# signal-board.net
KiCad netlist of a schematic drawn in EAGLE
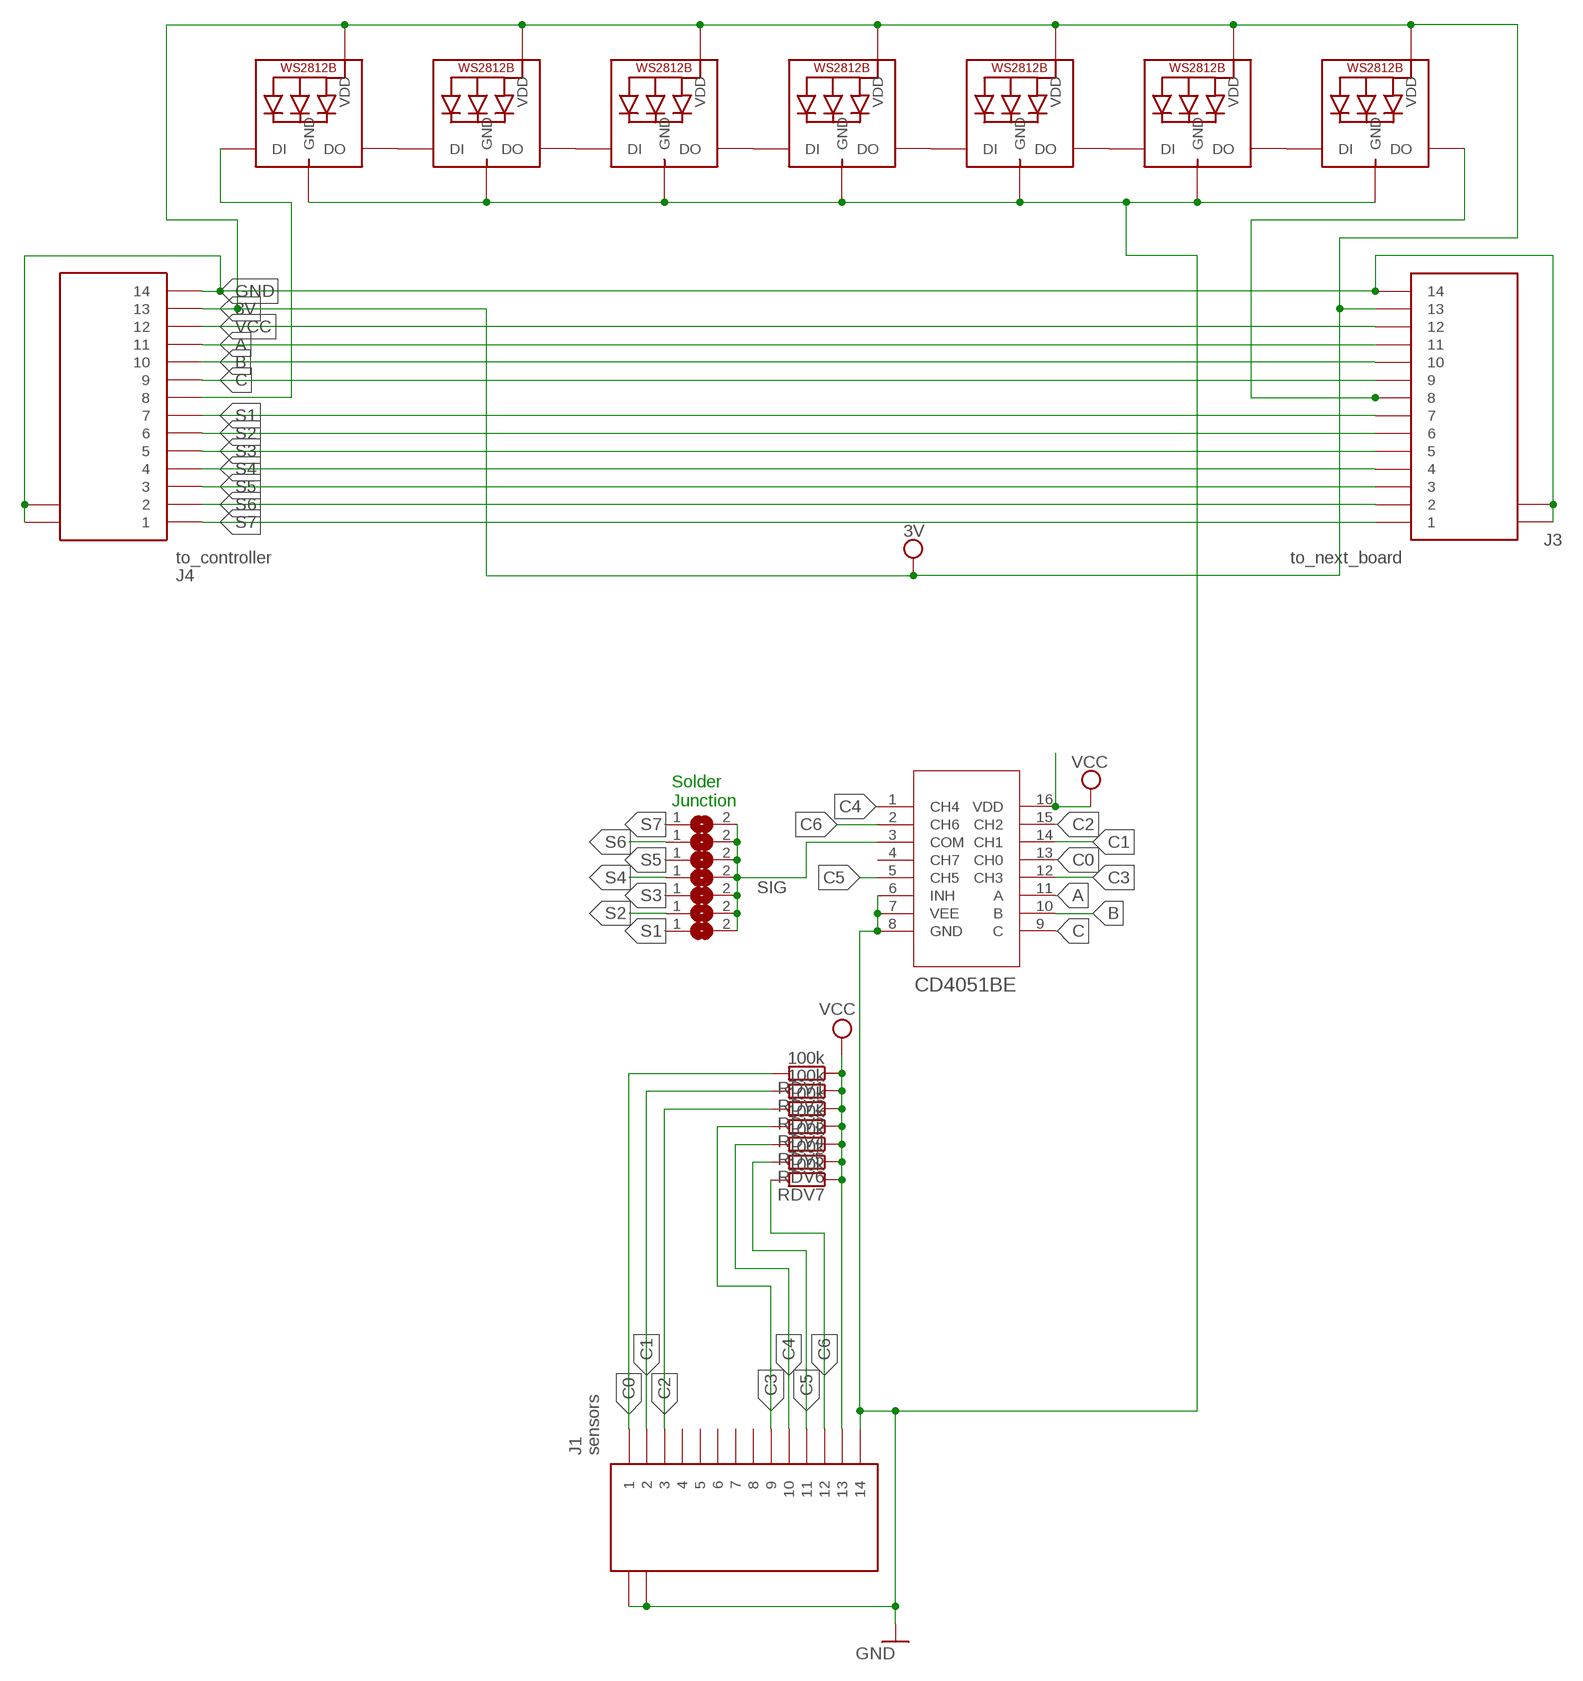
[diagram p0: schematic, sheet 1]

(export (version "E")
  (design (tool "Eeschema 10.0.6"))
  (components
    (comp (ref "J1")
      (value "sensors")
      (footprint "eagle-import:686114148922")
      (fields
        (field (name "MANUFACTURER_PART_NUMBER") "686114148922")
        (field (name "MOUSER_PART_NUMBER") "710-686114148922")
      )
      (libsource (lib "eagle-import") (part "686114148922"))
    )
    (comp (ref "J3")
      (value "to_next_board")
      (footprint "eagle-import:686114148922")
      (fields
        (field (name "MANUFACTURER_PART_NUMBER") "686114148922")
        (field (name "MOUSER_PART_NUMBER") "710-686114148922")
      )
      (libsource (lib "eagle-import") (part "686114148922"))
    )
    (comp (ref "J4")
      (value "to_controller")
      (footprint "eagle-import:686114148922")
      (fields
        (field (name "MANUFACTURER_PART_NUMBER") "686114148922")
        (field (name "MOUSER_PART_NUMBER") "710-686114148922")
      )
      (libsource (lib "eagle-import") (part "686114148922"))
    )
    (comp (ref "LED1")
      (value "WS2812B3535")
      (footprint "eagle-import:LED3535")
      (libsource (lib "eagle-import") (part "WS2812B3535"))
    )
    (comp (ref "LED2")
      (value "WS2812B3535")
      (footprint "eagle-import:LED3535")
      (libsource (lib "eagle-import") (part "WS2812B3535"))
    )
    (comp (ref "LED3")
      (value "WS2812B3535")
      (footprint "eagle-import:LED3535")
      (libsource (lib "eagle-import") (part "WS2812B3535"))
    )
    (comp (ref "LED4")
      (value "WS2812B3535")
      (footprint "eagle-import:LED3535")
      (libsource (lib "eagle-import") (part "WS2812B3535"))
    )
    (comp (ref "LED5")
      (value "WS2812B3535")
      (footprint "eagle-import:LED3535")
      (libsource (lib "eagle-import") (part "WS2812B3535"))
    )
    (comp (ref "LED6")
      (value "WS2812B3535")
      (footprint "eagle-import:LED3535")
      (libsource (lib "eagle-import") (part "WS2812B3535"))
    )
    (comp (ref "LED7")
      (value "WS2812B3535")
      (footprint "eagle-import:LED3535")
      (libsource (lib "eagle-import") (part "WS2812B3535"))
    )
    (comp (ref "RDV1")
      (value "100k")
      (footprint "eagle-import:0207_10")
      (libsource (lib "eagle-import") (part "R-EU_0207/10"))
    )
    (comp (ref "RDV2")
      (value "100k")
      (footprint "eagle-import:0207_10")
      (libsource (lib "eagle-import") (part "R-EU_0207/10"))
    )
    (comp (ref "RDV3")
      (value "100k")
      (footprint "eagle-import:0207_10")
      (libsource (lib "eagle-import") (part "R-EU_0207/10"))
    )
    (comp (ref "RDV4")
      (value "100k")
      (footprint "eagle-import:0207_10")
      (libsource (lib "eagle-import") (part "R-EU_0207/10"))
    )
    (comp (ref "RDV5")
      (value "100k")
      (footprint "eagle-import:0207_10")
      (libsource (lib "eagle-import") (part "R-EU_0207/10"))
    )
    (comp (ref "RDV6")
      (value "100k")
      (footprint "eagle-import:0207_10")
      (libsource (lib "eagle-import") (part "R-EU_0207/10"))
    )
    (comp (ref "RDV7")
      (value "100k")
      (footprint "eagle-import:0207_10")
      (libsource (lib "eagle-import") (part "R-EU_0207/10"))
    )
    (comp (ref "SJ1") (value "SJ") (footprint "eagle-import:SJ") (libsource (lib "eagle-import") (part "SJ")))
    (comp (ref "SJ2") (value "SJ") (footprint "eagle-import:SJ") (libsource (lib "eagle-import") (part "SJ")))
    (comp (ref "SJ3") (value "SJ") (footprint "eagle-import:SJ") (libsource (lib "eagle-import") (part "SJ")))
    (comp (ref "SJ4") (value "SJ") (footprint "eagle-import:SJ") (libsource (lib "eagle-import") (part "SJ")))
    (comp (ref "SJ5") (value "SJ") (footprint "eagle-import:SJ") (libsource (lib "eagle-import") (part "SJ")))
    (comp (ref "SJ6") (value "SJ") (footprint "eagle-import:SJ") (libsource (lib "eagle-import") (part "SJ")))
    (comp (ref "SJ7") (value "SJ") (footprint "eagle-import:SJ") (libsource (lib "eagle-import") (part "SJ")))
    (comp (ref "U1")
      (value "CD4051BE")
      (footprint "eagle-import:N16")
      (fields (field (name "COPYRIGHT") "Copyright (C) 2024 Ultra Librarian. All rights reserved."))
      (libsource (lib "eagle-import") (part "CD4051BE"))
    )
  )
  (nets
    (net (code "1") (name "/SIG") (class "Default")
      (node (ref "SJ1") (pin "2") (pinfunction "2_2") (pintype "passive"))
      (node (ref "SJ2") (pin "2") (pinfunction "2_2") (pintype "passive"))
      (node (ref "SJ3") (pin "2") (pinfunction "2_2") (pintype "passive"))
      (node (ref "SJ4") (pin "2") (pinfunction "2_2") (pintype "passive"))
      (node (ref "SJ5") (pin "2") (pinfunction "2_2") (pintype "passive"))
      (node (ref "SJ6") (pin "2") (pinfunction "2_2") (pintype "passive"))
      (node (ref "SJ7") (pin "2") (pinfunction "2_2") (pintype "passive"))
      (node (ref "U1") (pin "3") (pinfunction "COM_3") (pintype "bidirectional"))
    )
    (net (code "2") (name "3V") (class "Default")
      (node (ref "J3") (pin "13") (pinfunction "13_13") (pintype "bidirectional"))
      (node (ref "J4") (pin "13") (pinfunction "13_13") (pintype "bidirectional"))
      (node (ref "LED1") (pin "2") (pinfunction "VDD_2") (pintype "power_in"))
      (node (ref "LED2") (pin "2") (pinfunction "VDD_2") (pintype "power_in"))
      (node (ref "LED3") (pin "2") (pinfunction "VDD_2") (pintype "power_in"))
      (node (ref "LED4") (pin "2") (pinfunction "VDD_2") (pintype "power_in"))
      (node (ref "LED5") (pin "2") (pinfunction "VDD_2") (pintype "power_in"))
      (node (ref "LED6") (pin "2") (pinfunction "VDD_2") (pintype "power_in"))
      (node (ref "LED7") (pin "2") (pinfunction "VDD_2") (pintype "power_in"))
    )
    (net (code "3") (name "A") (class "Default")
      (node (ref "J3") (pin "11") (pinfunction "11_11") (pintype "bidirectional"))
      (node (ref "J4") (pin "11") (pinfunction "11_11") (pintype "bidirectional"))
      (node (ref "U1") (pin "11") (pinfunction "A_11") (pintype "passive"))
    )
    (net (code "4") (name "B") (class "Default")
      (node (ref "J3") (pin "10") (pinfunction "10_10") (pintype "bidirectional"))
      (node (ref "J4") (pin "10") (pinfunction "10_10") (pintype "bidirectional"))
      (node (ref "U1") (pin "10") (pinfunction "B_10") (pintype "passive"))
    )
    (net (code "5") (name "C") (class "Default")
      (node (ref "J3") (pin "9") (pinfunction "9_9") (pintype "bidirectional"))
      (node (ref "J4") (pin "9") (pinfunction "9_9") (pintype "bidirectional"))
      (node (ref "U1") (pin "9") (pinfunction "C_9") (pintype "passive"))
    )
    (net (code "6") (name "C0") (class "Default")
      (node (ref "J1") (pin "1") (pinfunction "1_1") (pintype "bidirectional"))
      (node (ref "RDV1") (pin "2") (pinfunction "2_2") (pintype "passive"))
      (node (ref "U1") (pin "13") (pinfunction "CH0_13") (pintype "bidirectional"))
    )
    (net (code "7") (name "C1") (class "Default")
      (node (ref "J1") (pin "2") (pinfunction "2_2") (pintype "bidirectional"))
      (node (ref "RDV2") (pin "2") (pinfunction "2_2") (pintype "passive"))
      (node (ref "U1") (pin "14") (pinfunction "CH1_14") (pintype "bidirectional"))
    )
    (net (code "8") (name "C2") (class "Default")
      (node (ref "J1") (pin "3") (pinfunction "3_3") (pintype "bidirectional"))
      (node (ref "RDV3") (pin "2") (pinfunction "2_2") (pintype "passive"))
      (node (ref "U1") (pin "15") (pinfunction "CH2_15") (pintype "bidirectional"))
    )
    (net (code "9") (name "C3") (class "Default")
      (node (ref "J1") (pin "9") (pinfunction "9_9") (pintype "bidirectional"))
      (node (ref "RDV4") (pin "2") (pinfunction "2_2") (pintype "passive"))
      (node (ref "U1") (pin "12") (pinfunction "CH3_12") (pintype "bidirectional"))
    )
    (net (code "10") (name "C4") (class "Default")
      (node (ref "J1") (pin "10") (pinfunction "10_10") (pintype "bidirectional"))
      (node (ref "RDV5") (pin "2") (pinfunction "2_2") (pintype "passive"))
      (node (ref "U1") (pin "1") (pinfunction "CH4_1") (pintype "bidirectional"))
    )
    (net (code "11") (name "C5") (class "Default")
      (node (ref "J1") (pin "11") (pinfunction "11_11") (pintype "bidirectional"))
      (node (ref "RDV6") (pin "2") (pinfunction "2_2") (pintype "passive"))
      (node (ref "U1") (pin "5") (pinfunction "CH5_5") (pintype "bidirectional"))
    )
    (net (code "12") (name "C6") (class "Default")
      (node (ref "J1") (pin "12") (pinfunction "12_12") (pintype "bidirectional"))
      (node (ref "RDV7") (pin "2") (pinfunction "2_2") (pintype "passive"))
      (node (ref "U1") (pin "2") (pinfunction "CH6_2") (pintype "bidirectional"))
    )
    (net (code "13") (name "GND") (class "Default")
      (node (ref "J1") (pin "14") (pinfunction "14_14") (pintype "bidirectional"))
      (node (ref "J1") (pin "MP1") (pinfunction "MP1_MP1") (pintype "bidirectional"))
      (node (ref "J1") (pin "MP2") (pinfunction "MP2_MP2") (pintype "bidirectional"))
      (node (ref "J3") (pin "14") (pinfunction "14_14") (pintype "bidirectional"))
      (node (ref "J3") (pin "MP1") (pinfunction "MP1_MP1") (pintype "bidirectional"))
      (node (ref "J3") (pin "MP2") (pinfunction "MP2_MP2") (pintype "bidirectional"))
      (node (ref "J4") (pin "14") (pinfunction "14_14") (pintype "bidirectional"))
      (node (ref "J4") (pin "MP1") (pinfunction "MP1_MP1") (pintype "bidirectional"))
      (node (ref "J4") (pin "MP2") (pinfunction "MP2_MP2") (pintype "bidirectional"))
      (node (ref "LED1") (pin "4") (pinfunction "GND_4") (pintype "power_in"))
      (node (ref "LED2") (pin "4") (pinfunction "GND_4") (pintype "power_in"))
      (node (ref "LED3") (pin "4") (pinfunction "GND_4") (pintype "power_in"))
      (node (ref "LED4") (pin "4") (pinfunction "GND_4") (pintype "power_in"))
      (node (ref "LED5") (pin "4") (pinfunction "GND_4") (pintype "power_in"))
      (node (ref "LED6") (pin "4") (pinfunction "GND_4") (pintype "power_in"))
      (node (ref "LED7") (pin "4") (pinfunction "GND_4") (pintype "power_in"))
      (node (ref "U1") (pin "6") (pinfunction "INH_6") (pintype "passive"))
      (node (ref "U1") (pin "7") (pinfunction "VEE_7") (pintype "power_in"))
      (node (ref "U1") (pin "8") (pinfunction "GND_8") (pintype "power_in"))
    )
    (net (code "14") (name "Net-(LED1-DI)") (class "Default")
      (node (ref "J4") (pin "8") (pinfunction "8_8") (pintype "bidirectional"))
      (node (ref "LED1") (pin "1") (pinfunction "DI_1") (pintype "input"))
    )
    (net (code "15") (name "Net-(LED1-DO)") (class "Default")
      (node (ref "LED1") (pin "3") (pinfunction "DO_3") (pintype "output"))
      (node (ref "LED2") (pin "1") (pinfunction "DI_1") (pintype "input"))
    )
    (net (code "16") (name "Net-(LED2-DO)") (class "Default")
      (node (ref "LED2") (pin "3") (pinfunction "DO_3") (pintype "output"))
      (node (ref "LED3") (pin "1") (pinfunction "DI_1") (pintype "input"))
    )
    (net (code "17") (name "Net-(LED3-DO)") (class "Default")
      (node (ref "LED3") (pin "3") (pinfunction "DO_3") (pintype "output"))
      (node (ref "LED4") (pin "1") (pinfunction "DI_1") (pintype "input"))
    )
    (net (code "18") (name "Net-(LED4-DO)") (class "Default")
      (node (ref "LED4") (pin "3") (pinfunction "DO_3") (pintype "output"))
      (node (ref "LED5") (pin "1") (pinfunction "DI_1") (pintype "input"))
    )
    (net (code "19") (name "Net-(LED5-DO)") (class "Default")
      (node (ref "LED5") (pin "3") (pinfunction "DO_3") (pintype "output"))
      (node (ref "LED6") (pin "1") (pinfunction "DI_1") (pintype "input"))
    )
    (net (code "20") (name "Net-(LED6-DO)") (class "Default")
      (node (ref "LED6") (pin "3") (pinfunction "DO_3") (pintype "output"))
      (node (ref "LED7") (pin "1") (pinfunction "DI_1") (pintype "input"))
    )
    (net (code "21") (name "Net-(LED7-DO)") (class "Default")
      (node (ref "J3") (pin "8") (pinfunction "8_8") (pintype "bidirectional"))
      (node (ref "LED7") (pin "3") (pinfunction "DO_3") (pintype "output"))
    )
    (net (code "22") (name "S1") (class "Default")
      (node (ref "J3") (pin "7") (pinfunction "7_7") (pintype "bidirectional"))
      (node (ref "J4") (pin "7") (pinfunction "7_7") (pintype "bidirectional"))
      (node (ref "SJ1") (pin "1") (pinfunction "1_1") (pintype "passive"))
    )
    (net (code "23") (name "S2") (class "Default")
      (node (ref "J3") (pin "6") (pinfunction "6_6") (pintype "bidirectional"))
      (node (ref "J4") (pin "6") (pinfunction "6_6") (pintype "bidirectional"))
      (node (ref "SJ2") (pin "1") (pinfunction "1_1") (pintype "passive"))
    )
    (net (code "24") (name "S3") (class "Default")
      (node (ref "J3") (pin "5") (pinfunction "5_5") (pintype "bidirectional"))
      (node (ref "J4") (pin "5") (pinfunction "5_5") (pintype "bidirectional"))
      (node (ref "SJ3") (pin "1") (pinfunction "1_1") (pintype "passive"))
    )
    (net (code "25") (name "S4") (class "Default")
      (node (ref "J3") (pin "4") (pinfunction "4_4") (pintype "bidirectional"))
      (node (ref "J4") (pin "4") (pinfunction "4_4") (pintype "bidirectional"))
      (node (ref "SJ4") (pin "1") (pinfunction "1_1") (pintype "passive"))
    )
    (net (code "26") (name "S5") (class "Default")
      (node (ref "J3") (pin "3") (pinfunction "3_3") (pintype "bidirectional"))
      (node (ref "J4") (pin "3") (pinfunction "3_3") (pintype "bidirectional"))
      (node (ref "SJ5") (pin "1") (pinfunction "1_1") (pintype "passive"))
    )
    (net (code "27") (name "S6") (class "Default")
      (node (ref "J3") (pin "2") (pinfunction "2_2") (pintype "bidirectional"))
      (node (ref "J4") (pin "2") (pinfunction "2_2") (pintype "bidirectional"))
      (node (ref "SJ6") (pin "1") (pinfunction "1_1") (pintype "passive"))
    )
    (net (code "28") (name "S7") (class "Default")
      (node (ref "J3") (pin "1") (pinfunction "1_1") (pintype "bidirectional"))
      (node (ref "J4") (pin "1") (pinfunction "1_1") (pintype "bidirectional"))
      (node (ref "SJ7") (pin "1") (pinfunction "1_1") (pintype "passive"))
    )
    (net (code "29") (name "VCC") (class "Default")
      (node (ref "J1") (pin "13") (pinfunction "13_13") (pintype "bidirectional"))
      (node (ref "J3") (pin "12") (pinfunction "12_12") (pintype "bidirectional"))
      (node (ref "J4") (pin "12") (pinfunction "12_12") (pintype "bidirectional"))
      (node (ref "RDV1") (pin "1") (pinfunction "1_1") (pintype "passive"))
      (node (ref "RDV2") (pin "1") (pinfunction "1_1") (pintype "passive"))
      (node (ref "RDV3") (pin "1") (pinfunction "1_1") (pintype "passive"))
      (node (ref "RDV4") (pin "1") (pinfunction "1_1") (pintype "passive"))
      (node (ref "RDV5") (pin "1") (pinfunction "1_1") (pintype "passive"))
      (node (ref "RDV6") (pin "1") (pinfunction "1_1") (pintype "passive"))
      (node (ref "RDV7") (pin "1") (pinfunction "1_1") (pintype "passive"))
      (node (ref "U1") (pin "16") (pinfunction "VDD_16") (pintype "power_in"))
    )
    (net (code "30") (name "unconnected-(J1-Pad4)") (class "Default")
      (node (ref "J1") (pin "4") (pinfunction "4_4") (pintype "bidirectional"))
    )
    (net (code "31") (name "unconnected-(J1-Pad5)") (class "Default")
      (node (ref "J1") (pin "5") (pinfunction "5_5") (pintype "bidirectional"))
    )
    (net (code "32") (name "unconnected-(J1-Pad6)") (class "Default")
      (node (ref "J1") (pin "6") (pinfunction "6_6") (pintype "bidirectional"))
    )
    (net (code "33") (name "unconnected-(J1-Pad7)") (class "Default")
      (node (ref "J1") (pin "7") (pinfunction "7_7") (pintype "bidirectional"))
    )
    (net (code "34") (name "unconnected-(J1-Pad8)") (class "Default")
      (node (ref "J1") (pin "8") (pinfunction "8_8") (pintype "bidirectional"))
    )
    (net (code "35") (name "unconnected-(U1-CH7-Pad4)") (class "Default")
      (node (ref "U1") (pin "4") (pinfunction "CH7_4") (pintype "bidirectional"))
    )
  )
)
